# TurboMaster-optimized.net
KiCad netlist of a schematic drawn in EAGLE
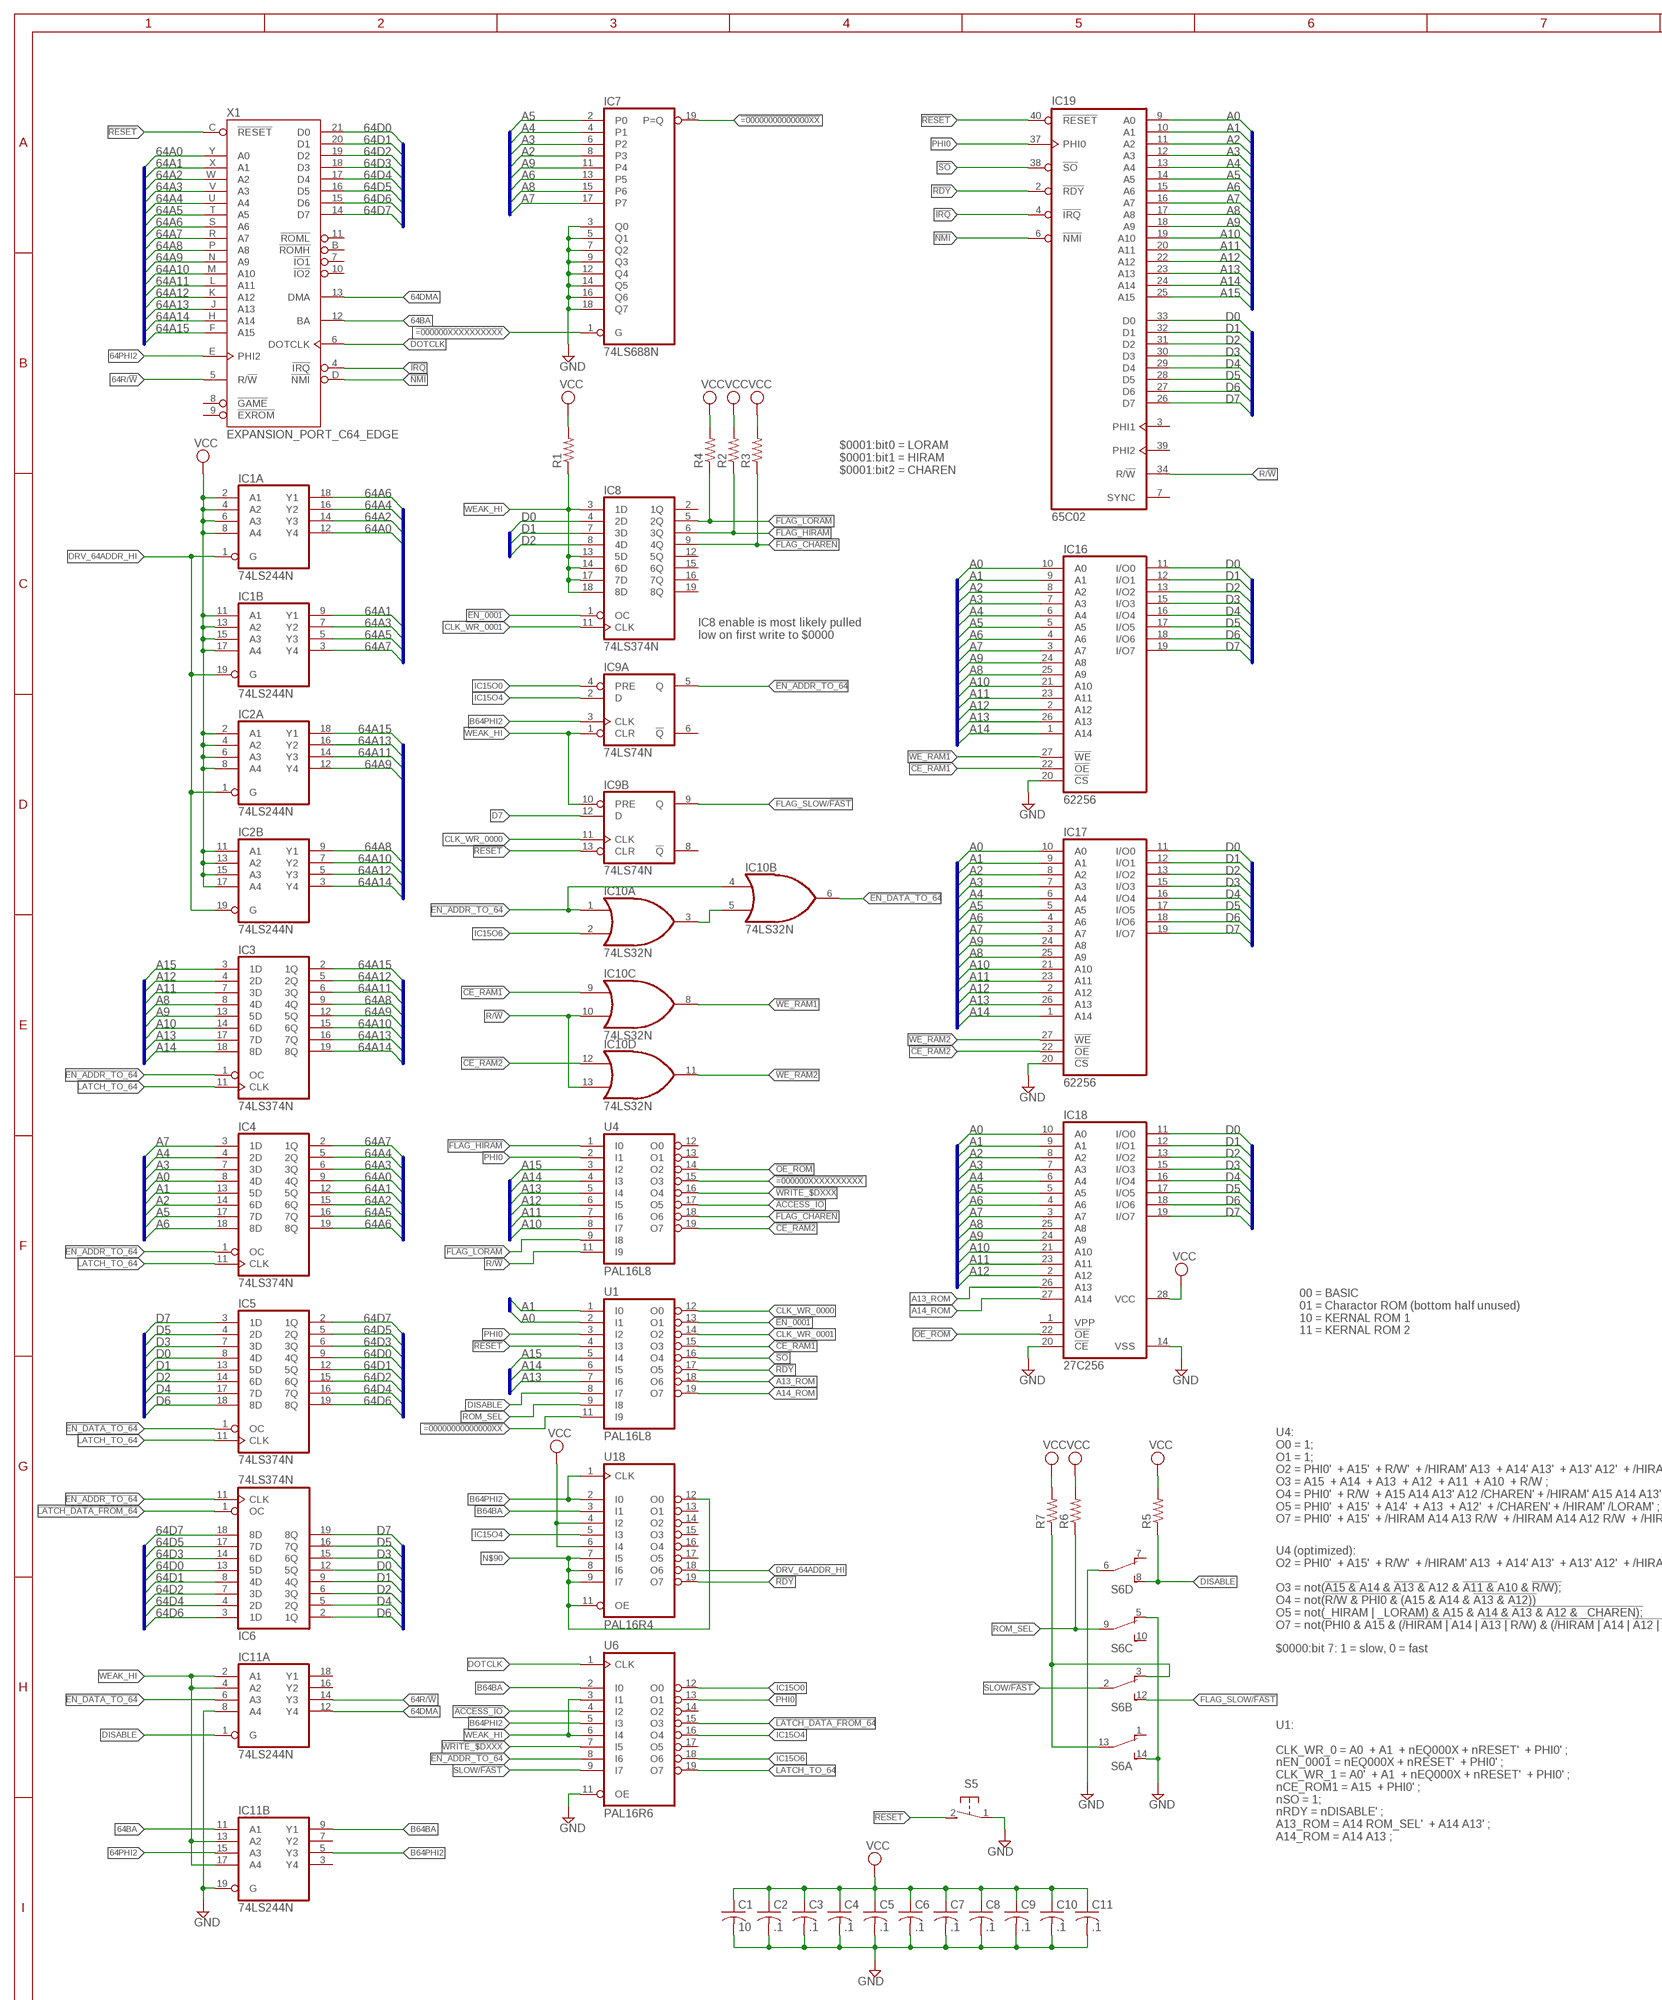
[diagram p0: schematic, sheet 1, part 1 of 2]
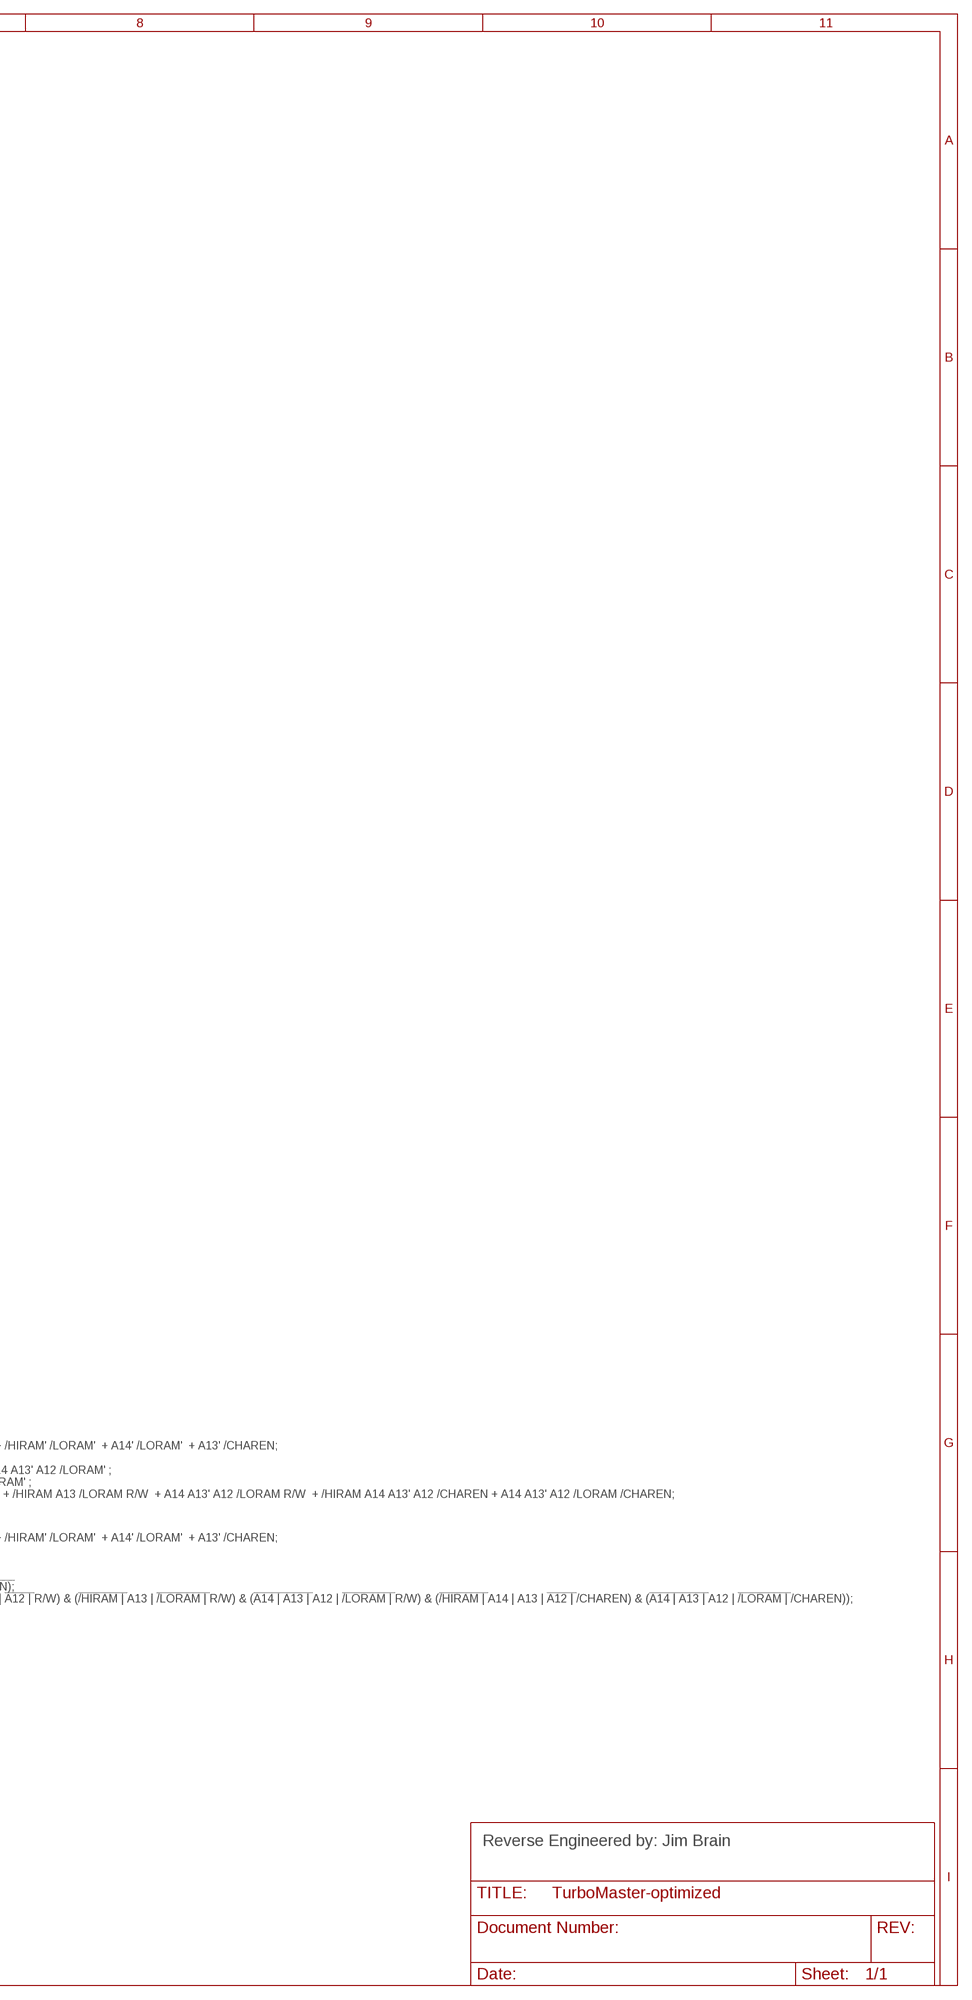
[diagram p1: schematic, sheet 1, part 2 of 2]

(export (version "E")
  (design (tool "Eeschema 10.0.6"))
  (components
    (comp (ref "C1")
      (value "10")
      (footprint "eagle-import:C050-024X044")
      (libsource (lib "eagle-import") (part "C-US050-024X044"))
    )
    (comp (ref "C2")
      (value ".1")
      (footprint "eagle-import:C050-024X044")
      (libsource (lib "eagle-import") (part "C-US050-024X044"))
    )
    (comp (ref "C3")
      (value ".1")
      (footprint "eagle-import:C050-024X044")
      (libsource (lib "eagle-import") (part "C-US050-024X044"))
    )
    (comp (ref "C4")
      (value ".1")
      (footprint "eagle-import:C050-024X044")
      (libsource (lib "eagle-import") (part "C-US050-024X044"))
    )
    (comp (ref "C5")
      (value ".1")
      (footprint "eagle-import:C050-024X044")
      (libsource (lib "eagle-import") (part "C-US050-024X044"))
    )
    (comp (ref "C6")
      (value ".1")
      (footprint "eagle-import:C050-024X044")
      (libsource (lib "eagle-import") (part "C-US050-024X044"))
    )
    (comp (ref "C7")
      (value ".1")
      (footprint "eagle-import:C050-024X044")
      (libsource (lib "eagle-import") (part "C-US050-024X044"))
    )
    (comp (ref "C8")
      (value ".1")
      (footprint "eagle-import:C050-024X044")
      (libsource (lib "eagle-import") (part "C-US050-024X044"))
    )
    (comp (ref "C9")
      (value ".1")
      (footprint "eagle-import:C050-024X044")
      (libsource (lib "eagle-import") (part "C-US050-024X044"))
    )
    (comp (ref "C10")
      (value ".1")
      (footprint "eagle-import:C050-024X044")
      (libsource (lib "eagle-import") (part "C-US050-024X044"))
    )
    (comp (ref "C11")
      (value ".1")
      (footprint "eagle-import:C050-024X044")
      (libsource (lib "eagle-import") (part "C-US050-024X044"))
    )
    (comp (ref "IC1")
      (value "74LS244N")
      (footprint "eagle-import:DIL20")
      (libsource (lib "eagle-import") (part "74244NLS"))
    )
    (comp (ref "IC2")
      (value "74LS244N")
      (footprint "eagle-import:DIL20")
      (libsource (lib "eagle-import") (part "74244NLS"))
    )
    (comp (ref "IC3")
      (value "74LS374N")
      (footprint "eagle-import:DIL20")
      (libsource (lib "eagle-import") (part "74374NLS"))
    )
    (comp (ref "IC4")
      (value "74LS374N")
      (footprint "eagle-import:DIL20")
      (libsource (lib "eagle-import") (part "74374NLS"))
    )
    (comp (ref "IC5")
      (value "74LS374N")
      (footprint "eagle-import:DIL20")
      (libsource (lib "eagle-import") (part "74374NLS"))
    )
    (comp (ref "IC6")
      (value "74LS374N")
      (footprint "eagle-import:DIL20")
      (libsource (lib "eagle-import") (part "74374NLS"))
    )
    (comp (ref "IC7")
      (value "74LS688N")
      (footprint "eagle-import:DIL20")
      (libsource (lib "eagle-import") (part "74688NLS"))
    )
    (comp (ref "IC8")
      (value "74LS374N")
      (footprint "eagle-import:DIL20")
      (libsource (lib "eagle-import") (part "74374NLS"))
    )
    (comp (ref "IC9")
      (value "74LS74N")
      (footprint "eagle-import:DIL14")
      (libsource (lib "eagle-import") (part "7474NLS"))
    )
    (comp (ref "IC10")
      (value "74LS32N")
      (footprint "eagle-import:DIL14")
      (libsource (lib "eagle-import") (part "7432NLS"))
    )
    (comp (ref "IC11")
      (value "74LS244N")
      (footprint "eagle-import:DIL20")
      (libsource (lib "eagle-import") (part "74244NLS"))
    )
    (comp (ref "IC16")
      (value "62256")
      (footprint "eagle-import:DIL28")
      (libsource (lib "eagle-import") (part "62256"))
    )
    (comp (ref "IC17")
      (value "62256")
      (footprint "eagle-import:DIL28")
      (libsource (lib "eagle-import") (part "62256"))
    )
    (comp (ref "IC18")
      (value "27C256")
      (footprint "eagle-import:DIL28-6")
      (libsource (lib "eagle-import") (part "27C256AG"))
    )
    (comp (ref "IC19")
      (value "65C02")
      (footprint "eagle-import:DIL40")
      (libsource (lib "eagle-import") (part "6502C"))
    )
    (comp (ref "R1")
      (value "R-US_0207/10")
      (footprint "eagle-import:0207_10")
      (libsource (lib "eagle-import") (part "R-US_0207/10"))
    )
    (comp (ref "R2")
      (value "R-US_0207/10")
      (footprint "eagle-import:0207_10")
      (libsource (lib "eagle-import") (part "R-US_0207/10"))
    )
    (comp (ref "R3")
      (value "R-US_0207/10")
      (footprint "eagle-import:0207_10")
      (libsource (lib "eagle-import") (part "R-US_0207/10"))
    )
    (comp (ref "R4")
      (value "R-US_0207/10")
      (footprint "eagle-import:0207_10")
      (libsource (lib "eagle-import") (part "R-US_0207/10"))
    )
    (comp (ref "R5")
      (value "R-US_0207/10")
      (footprint "eagle-import:0207_10")
      (libsource (lib "eagle-import") (part "R-US_0207/10"))
    )
    (comp (ref "R6")
      (value "R-US_0207/10")
      (footprint "eagle-import:0207_10")
      (libsource (lib "eagle-import") (part "R-US_0207/10"))
    )
    (comp (ref "R7")
      (value "R-US_0207/10")
      (footprint "eagle-import:0207_10")
      (libsource (lib "eagle-import") (part "R-US_0207/10"))
    )
    (comp (ref "S5")
      (value "31-XX")
      (footprint "eagle-import:B3F-31XX")
      (fields (field (name "MPN") "B3F-3100"))
      (libsource (lib "eagle-import") (part "31-XX"))
    )
    (comp (ref "S6")
      (value "DIP04DPDTS")
      (footprint "eagle-import:DIP04DPDTS")
      (libsource (lib "eagle-import") (part "DIP04DPDTS"))
    )
    (comp (ref "U1")
      (value "PAL16L8")
      (footprint "eagle-import:DIL20")
      (fields (field (name "MF") "TEXAS INSTRUMENTS") (field (name "MPN") "TIBPAL16L8-7CN"))
      (libsource (lib "eagle-import") (part "16L8"))
    )
    (comp (ref "U4")
      (value "PAL16L8")
      (footprint "eagle-import:DIL20")
      (fields (field (name "MF") "TEXAS INSTRUMENTS") (field (name "MPN") "TIBPAL16L8-7CN"))
      (libsource (lib "eagle-import") (part "16L8"))
    )
    (comp (ref "U6")
      (value "PAL16R6")
      (footprint "eagle-import:DIL20")
      (fields (field (name "MPN") "TIBPAL16R6-10CN"))
      (libsource (lib "eagle-import") (part "16R6"))
    )
    (comp (ref "U18")
      (value "PAL16R4")
      (footprint "eagle-import:DIL20")
      (fields (field (name "MF") "TEXAS INSTRUMENTS") (field (name "MPN") "TIBPAL16R4-10CN"))
      (libsource (lib "eagle-import") (part "16R4"))
    )
    (comp (ref "X1")
      (value "EXPANSION_PORT_C64_EDGE")
      (footprint "eagle-import:MA100-22-2")
      (libsource (lib "eagle-import") (part "EXPANSION_PORT_C64_EDGE"))
    )
  )
  (nets
    (net (code "1") (name "/64A0") (class "Default")
      (node (ref "IC1") (pin "12") (pinfunction "Y4_12") (pintype "tri_state"))
      (node (ref "IC4") (pin "9") (pinfunction "4Q_9") (pintype "tri_state"))
      (node (ref "X1") (pin "Y") (pinfunction "A0_Y") (pintype "bidirectional"))
    )
    (net (code "2") (name "/64A1") (class "Default")
      (node (ref "IC1") (pin "9") (pinfunction "Y1_9") (pintype "tri_state"))
      (node (ref "IC4") (pin "12") (pinfunction "5Q_12") (pintype "tri_state"))
      (node (ref "X1") (pin "X") (pinfunction "A1_X") (pintype "bidirectional"))
    )
    (net (code "3") (name "/64A2") (class "Default")
      (node (ref "IC1") (pin "14") (pinfunction "Y3_14") (pintype "tri_state"))
      (node (ref "IC4") (pin "15") (pinfunction "6Q_15") (pintype "tri_state"))
      (node (ref "X1") (pin "W") (pinfunction "A2_W") (pintype "bidirectional"))
    )
    (net (code "4") (name "/64A3") (class "Default")
      (node (ref "IC1") (pin "7") (pinfunction "Y2_7") (pintype "tri_state"))
      (node (ref "IC4") (pin "6") (pinfunction "3Q_6") (pintype "tri_state"))
      (node (ref "X1") (pin "V") (pinfunction "A3_V") (pintype "bidirectional"))
    )
    (net (code "5") (name "/64A4") (class "Default")
      (node (ref "IC1") (pin "16") (pinfunction "Y2_16") (pintype "tri_state"))
      (node (ref "IC4") (pin "5") (pinfunction "2Q_5") (pintype "tri_state"))
      (node (ref "X1") (pin "U") (pinfunction "A4_U") (pintype "bidirectional"))
    )
    (net (code "6") (name "/64A5") (class "Default")
      (node (ref "IC1") (pin "5") (pinfunction "Y3_5") (pintype "tri_state"))
      (node (ref "IC4") (pin "16") (pinfunction "7Q_16") (pintype "tri_state"))
      (node (ref "X1") (pin "T") (pinfunction "A5_T") (pintype "bidirectional"))
    )
    (net (code "7") (name "/64A6") (class "Default")
      (node (ref "IC1") (pin "18") (pinfunction "Y1_18") (pintype "tri_state"))
      (node (ref "IC4") (pin "19") (pinfunction "8Q_19") (pintype "tri_state"))
      (node (ref "X1") (pin "S") (pinfunction "A6_S") (pintype "bidirectional"))
    )
    (net (code "8") (name "/64A7") (class "Default")
      (node (ref "IC1") (pin "3") (pinfunction "Y4_3") (pintype "tri_state"))
      (node (ref "IC4") (pin "2") (pinfunction "1Q_2") (pintype "tri_state"))
      (node (ref "X1") (pin "R") (pinfunction "A7_R") (pintype "bidirectional"))
    )
    (net (code "9") (name "/64A8") (class "Default")
      (node (ref "IC2") (pin "9") (pinfunction "Y1_9") (pintype "tri_state"))
      (node (ref "IC3") (pin "9") (pinfunction "4Q_9") (pintype "tri_state"))
      (node (ref "X1") (pin "P") (pinfunction "A8_P") (pintype "bidirectional"))
    )
    (net (code "10") (name "/64A9") (class "Default")
      (node (ref "IC2") (pin "12") (pinfunction "Y4_12") (pintype "tri_state"))
      (node (ref "IC3") (pin "12") (pinfunction "5Q_12") (pintype "tri_state"))
      (node (ref "X1") (pin "N") (pinfunction "A9_N") (pintype "bidirectional"))
    )
    (net (code "11") (name "/64A10") (class "Default")
      (node (ref "IC2") (pin "7") (pinfunction "Y2_7") (pintype "tri_state"))
      (node (ref "IC3") (pin "15") (pinfunction "6Q_15") (pintype "tri_state"))
      (node (ref "X1") (pin "M") (pinfunction "A10_M") (pintype "bidirectional"))
    )
    (net (code "12") (name "/64A11") (class "Default")
      (node (ref "IC2") (pin "14") (pinfunction "Y3_14") (pintype "tri_state"))
      (node (ref "IC3") (pin "6") (pinfunction "3Q_6") (pintype "tri_state"))
      (node (ref "X1") (pin "L") (pinfunction "A11_L") (pintype "bidirectional"))
    )
    (net (code "13") (name "/64A12") (class "Default")
      (node (ref "IC2") (pin "5") (pinfunction "Y3_5") (pintype "tri_state"))
      (node (ref "IC3") (pin "5") (pinfunction "2Q_5") (pintype "tri_state"))
      (node (ref "X1") (pin "K") (pinfunction "A12_K") (pintype "bidirectional"))
    )
    (net (code "14") (name "/64A13") (class "Default")
      (node (ref "IC2") (pin "16") (pinfunction "Y2_16") (pintype "tri_state"))
      (node (ref "IC3") (pin "16") (pinfunction "7Q_16") (pintype "tri_state"))
      (node (ref "X1") (pin "J") (pinfunction "A13_J") (pintype "bidirectional"))
    )
    (net (code "15") (name "/64A14") (class "Default")
      (node (ref "IC2") (pin "3") (pinfunction "Y4_3") (pintype "tri_state"))
      (node (ref "IC3") (pin "19") (pinfunction "8Q_19") (pintype "tri_state"))
      (node (ref "X1") (pin "H") (pinfunction "A14_H") (pintype "bidirectional"))
    )
    (net (code "16") (name "/64A15") (class "Default")
      (node (ref "IC2") (pin "18") (pinfunction "Y1_18") (pintype "tri_state"))
      (node (ref "IC3") (pin "2") (pinfunction "1Q_2") (pintype "tri_state"))
      (node (ref "X1") (pin "F") (pinfunction "A15_F") (pintype "bidirectional"))
    )
    (net (code "17") (name "/64D0") (class "Default")
      (node (ref "IC5") (pin "9") (pinfunction "4Q_9") (pintype "tri_state"))
      (node (ref "IC6") (pin "13") (pinfunction "5D_13") (pintype "input"))
      (node (ref "X1") (pin "21") (pinfunction "D0_21") (pintype "bidirectional"))
    )
    (net (code "18") (name "/64D1") (class "Default")
      (node (ref "IC5") (pin "12") (pinfunction "5Q_12") (pintype "tri_state"))
      (node (ref "IC6") (pin "8") (pinfunction "4D_8") (pintype "input"))
      (node (ref "X1") (pin "20") (pinfunction "D1_20") (pintype "bidirectional"))
    )
    (net (code "19") (name "/64D2") (class "Default")
      (node (ref "IC5") (pin "15") (pinfunction "6Q_15") (pintype "tri_state"))
      (node (ref "IC6") (pin "7") (pinfunction "3D_7") (pintype "input"))
      (node (ref "X1") (pin "19") (pinfunction "D2_19") (pintype "bidirectional"))
    )
    (net (code "20") (name "/64D3") (class "Default")
      (node (ref "IC5") (pin "6") (pinfunction "3Q_6") (pintype "tri_state"))
      (node (ref "IC6") (pin "14") (pinfunction "6D_14") (pintype "input"))
      (node (ref "X1") (pin "18") (pinfunction "D3_18") (pintype "bidirectional"))
    )
    (net (code "21") (name "/64D4") (class "Default")
      (node (ref "IC5") (pin "16") (pinfunction "7Q_16") (pintype "tri_state"))
      (node (ref "IC6") (pin "4") (pinfunction "2D_4") (pintype "input"))
      (node (ref "X1") (pin "17") (pinfunction "D4_17") (pintype "bidirectional"))
    )
    (net (code "22") (name "/64D5") (class "Default")
      (node (ref "IC5") (pin "5") (pinfunction "2Q_5") (pintype "tri_state"))
      (node (ref "IC6") (pin "17") (pinfunction "7D_17") (pintype "input"))
      (node (ref "X1") (pin "16") (pinfunction "D5_16") (pintype "bidirectional"))
    )
    (net (code "23") (name "/64D6") (class "Default")
      (node (ref "IC5") (pin "19") (pinfunction "8Q_19") (pintype "tri_state"))
      (node (ref "IC6") (pin "3") (pinfunction "1D_3") (pintype "input"))
      (node (ref "X1") (pin "15") (pinfunction "D6_15") (pintype "bidirectional"))
    )
    (net (code "24") (name "/64D7") (class "Default")
      (node (ref "IC5") (pin "2") (pinfunction "1Q_2") (pintype "tri_state"))
      (node (ref "IC6") (pin "18") (pinfunction "8D_18") (pintype "input"))
      (node (ref "X1") (pin "14") (pinfunction "D7_14") (pintype "bidirectional"))
    )
    (net (code "25") (name "/64R{slash}~{W}") (class "Default")
      (node (ref "IC11") (pin "14") (pinfunction "Y3_14") (pintype "tri_state"))
      (node (ref "X1") (pin "5") (pinfunction "R/~{W}_5") (pintype "bidirectional"))
    )
    (net (code "26") (name "/A0") (class "Default")
      (node (ref "IC16") (pin "10") (pinfunction "A0_10") (pintype "input"))
      (node (ref "IC17") (pin "10") (pinfunction "A0_10") (pintype "input"))
      (node (ref "IC18") (pin "10") (pinfunction "A0_10") (pintype "input"))
      (node (ref "IC19") (pin "9") (pinfunction "A0_9") (pintype "output"))
      (node (ref "IC4") (pin "8") (pinfunction "4D_8") (pintype "input"))
      (node (ref "U1") (pin "2") (pinfunction "I1_2") (pintype "input"))
    )
    (net (code "27") (name "/A1") (class "Default")
      (node (ref "IC16") (pin "9") (pinfunction "A1_9") (pintype "input"))
      (node (ref "IC17") (pin "9") (pinfunction "A1_9") (pintype "input"))
      (node (ref "IC18") (pin "9") (pinfunction "A1_9") (pintype "input"))
      (node (ref "IC19") (pin "10") (pinfunction "A1_10") (pintype "output"))
      (node (ref "IC4") (pin "13") (pinfunction "5D_13") (pintype "input"))
      (node (ref "U1") (pin "1") (pinfunction "I0_1") (pintype "input"))
    )
    (net (code "28") (name "/A2") (class "Default")
      (node (ref "IC16") (pin "8") (pinfunction "A2_8") (pintype "input"))
      (node (ref "IC17") (pin "8") (pinfunction "A2_8") (pintype "input"))
      (node (ref "IC18") (pin "8") (pinfunction "A2_8") (pintype "input"))
      (node (ref "IC19") (pin "11") (pinfunction "A2_11") (pintype "output"))
      (node (ref "IC4") (pin "14") (pinfunction "6D_14") (pintype "input"))
      (node (ref "IC7") (pin "8") (pinfunction "P3_8") (pintype "input"))
    )
    (net (code "29") (name "/A3") (class "Default")
      (node (ref "IC16") (pin "7") (pinfunction "A3_7") (pintype "input"))
      (node (ref "IC17") (pin "7") (pinfunction "A3_7") (pintype "input"))
      (node (ref "IC18") (pin "7") (pinfunction "A3_7") (pintype "input"))
      (node (ref "IC19") (pin "12") (pinfunction "A3_12") (pintype "output"))
      (node (ref "IC4") (pin "7") (pinfunction "3D_7") (pintype "input"))
      (node (ref "IC7") (pin "6") (pinfunction "P2_6") (pintype "input"))
    )
    (net (code "30") (name "/A4") (class "Default")
      (node (ref "IC16") (pin "6") (pinfunction "A4_6") (pintype "input"))
      (node (ref "IC17") (pin "6") (pinfunction "A4_6") (pintype "input"))
      (node (ref "IC18") (pin "6") (pinfunction "A4_6") (pintype "input"))
      (node (ref "IC19") (pin "13") (pinfunction "A4_13") (pintype "output"))
      (node (ref "IC4") (pin "4") (pinfunction "2D_4") (pintype "input"))
      (node (ref "IC7") (pin "4") (pinfunction "P1_4") (pintype "input"))
    )
    (net (code "31") (name "/A5") (class "Default")
      (node (ref "IC16") (pin "5") (pinfunction "A5_5") (pintype "input"))
      (node (ref "IC17") (pin "5") (pinfunction "A5_5") (pintype "input"))
      (node (ref "IC18") (pin "5") (pinfunction "A5_5") (pintype "input"))
      (node (ref "IC19") (pin "14") (pinfunction "A5_14") (pintype "output"))
      (node (ref "IC4") (pin "17") (pinfunction "7D_17") (pintype "input"))
      (node (ref "IC7") (pin "2") (pinfunction "P0_2") (pintype "input"))
    )
    (net (code "32") (name "/A6") (class "Default")
      (node (ref "IC16") (pin "4") (pinfunction "A6_4") (pintype "input"))
      (node (ref "IC17") (pin "4") (pinfunction "A6_4") (pintype "input"))
      (node (ref "IC18") (pin "4") (pinfunction "A6_4") (pintype "input"))
      (node (ref "IC19") (pin "15") (pinfunction "A6_15") (pintype "output"))
      (node (ref "IC4") (pin "18") (pinfunction "8D_18") (pintype "input"))
      (node (ref "IC7") (pin "13") (pinfunction "P5_13") (pintype "input"))
    )
    (net (code "33") (name "/A7") (class "Default")
      (node (ref "IC16") (pin "3") (pinfunction "A7_3") (pintype "input"))
      (node (ref "IC17") (pin "3") (pinfunction "A7_3") (pintype "input"))
      (node (ref "IC18") (pin "3") (pinfunction "A7_3") (pintype "input"))
      (node (ref "IC19") (pin "16") (pinfunction "A7_16") (pintype "output"))
      (node (ref "IC4") (pin "3") (pinfunction "1D_3") (pintype "input"))
      (node (ref "IC7") (pin "17") (pinfunction "P7_17") (pintype "input"))
    )
    (net (code "34") (name "/A8") (class "Default")
      (node (ref "IC16") (pin "25") (pinfunction "A9_25") (pintype "input"))
      (node (ref "IC17") (pin "25") (pinfunction "A9_25") (pintype "input"))
      (node (ref "IC18") (pin "25") (pinfunction "A8_25") (pintype "input"))
      (node (ref "IC19") (pin "17") (pinfunction "A8_17") (pintype "output"))
      (node (ref "IC3") (pin "8") (pinfunction "4D_8") (pintype "input"))
      (node (ref "IC7") (pin "15") (pinfunction "P6_15") (pintype "input"))
    )
    (net (code "35") (name "/A9") (class "Default")
      (node (ref "IC16") (pin "24") (pinfunction "A8_24") (pintype "input"))
      (node (ref "IC17") (pin "24") (pinfunction "A8_24") (pintype "input"))
      (node (ref "IC18") (pin "24") (pinfunction "A9_24") (pintype "input"))
      (node (ref "IC19") (pin "18") (pinfunction "A9_18") (pintype "output"))
      (node (ref "IC3") (pin "13") (pinfunction "5D_13") (pintype "input"))
      (node (ref "IC7") (pin "11") (pinfunction "P4_11") (pintype "input"))
    )
    (net (code "36") (name "/A10") (class "Default")
      (node (ref "IC16") (pin "21") (pinfunction "A10_21") (pintype "input"))
      (node (ref "IC17") (pin "21") (pinfunction "A10_21") (pintype "input"))
      (node (ref "IC18") (pin "21") (pinfunction "A10_21") (pintype "input"))
      (node (ref "IC19") (pin "19") (pinfunction "A10_19") (pintype "output"))
      (node (ref "IC3") (pin "14") (pinfunction "6D_14") (pintype "input"))
      (node (ref "U4") (pin "8") (pinfunction "I7_8") (pintype "input"))
    )
    (net (code "37") (name "/A11") (class "Default")
      (node (ref "IC16") (pin "23") (pinfunction "A11_23") (pintype "input"))
      (node (ref "IC17") (pin "23") (pinfunction "A11_23") (pintype "input"))
      (node (ref "IC18") (pin "23") (pinfunction "A11_23") (pintype "input"))
      (node (ref "IC19") (pin "20") (pinfunction "A11_20") (pintype "output"))
      (node (ref "IC3") (pin "7") (pinfunction "3D_7") (pintype "input"))
      (node (ref "U4") (pin "7") (pinfunction "I6_7") (pintype "input"))
    )
    (net (code "38") (name "/A12") (class "Default")
      (node (ref "IC16") (pin "2") (pinfunction "A12_2") (pintype "input"))
      (node (ref "IC17") (pin "2") (pinfunction "A12_2") (pintype "input"))
      (node (ref "IC18") (pin "2") (pinfunction "A12_2") (pintype "input"))
      (node (ref "IC19") (pin "22") (pinfunction "A12_22") (pintype "output"))
      (node (ref "IC3") (pin "4") (pinfunction "2D_4") (pintype "input"))
      (node (ref "U4") (pin "6") (pinfunction "I5_6") (pintype "input"))
    )
    (net (code "39") (name "/A13") (class "Default")
      (node (ref "IC16") (pin "26") (pinfunction "A13_26") (pintype "input"))
      (node (ref "IC17") (pin "26") (pinfunction "A13_26") (pintype "input"))
      (node (ref "IC19") (pin "23") (pinfunction "A13_23") (pintype "output"))
      (node (ref "IC3") (pin "17") (pinfunction "7D_17") (pintype "input"))
      (node (ref "U1") (pin "7") (pinfunction "I6_7") (pintype "input"))
      (node (ref "U4") (pin "5") (pinfunction "I4_5") (pintype "input"))
    )
    (net (code "40") (name "/A14") (class "Default")
      (node (ref "IC16") (pin "1") (pinfunction "A14_1") (pintype "input"))
      (node (ref "IC17") (pin "1") (pinfunction "A14_1") (pintype "input"))
      (node (ref "IC19") (pin "24") (pinfunction "A14_24") (pintype "output"))
      (node (ref "IC3") (pin "18") (pinfunction "8D_18") (pintype "input"))
      (node (ref "U1") (pin "6") (pinfunction "I5_6") (pintype "input"))
      (node (ref "U4") (pin "4") (pinfunction "I3_4") (pintype "input"))
    )
    (net (code "41") (name "/A15") (class "Default")
      (node (ref "IC19") (pin "25") (pinfunction "A15_25") (pintype "output"))
      (node (ref "IC3") (pin "3") (pinfunction "1D_3") (pintype "input"))
      (node (ref "U1") (pin "5") (pinfunction "I4_5") (pintype "input"))
      (node (ref "U4") (pin "3") (pinfunction "I2_3") (pintype "input"))
    )
    (net (code "42") (name "/D0") (class "Default")
      (node (ref "IC16") (pin "11") (pinfunction "I/O0_11") (pintype "bidirectional"))
      (node (ref "IC17") (pin "11") (pinfunction "I/O0_11") (pintype "bidirectional"))
      (node (ref "IC18") (pin "11") (pinfunction "I/O0_11") (pintype "tri_state"))
      (node (ref "IC19") (pin "33") (pinfunction "D0_33") (pintype "bidirectional"))
      (node (ref "IC5") (pin "8") (pinfunction "4D_8") (pintype "input"))
      (node (ref "IC6") (pin "12") (pinfunction "5Q_12") (pintype "tri_state"))
      (node (ref "IC8") (pin "4") (pinfunction "2D_4") (pintype "input"))
    )
    (net (code "43") (name "/D1") (class "Default")
      (node (ref "IC16") (pin "12") (pinfunction "I/O1_12") (pintype "bidirectional"))
      (node (ref "IC17") (pin "12") (pinfunction "I/O1_12") (pintype "bidirectional"))
      (node (ref "IC18") (pin "12") (pinfunction "I/O1_12") (pintype "tri_state"))
      (node (ref "IC19") (pin "32") (pinfunction "D1_32") (pintype "bidirectional"))
      (node (ref "IC5") (pin "13") (pinfunction "5D_13") (pintype "input"))
      (node (ref "IC6") (pin "9") (pinfunction "4Q_9") (pintype "tri_state"))
      (node (ref "IC8") (pin "7") (pinfunction "3D_7") (pintype "input"))
    )
    (net (code "44") (name "/D2") (class "Default")
      (node (ref "IC16") (pin "13") (pinfunction "I/O2_13") (pintype "bidirectional"))
      (node (ref "IC17") (pin "13") (pinfunction "I/O2_13") (pintype "bidirectional"))
      (node (ref "IC18") (pin "13") (pinfunction "I/O2_13") (pintype "tri_state"))
      (node (ref "IC19") (pin "31") (pinfunction "D2_31") (pintype "bidirectional"))
      (node (ref "IC5") (pin "14") (pinfunction "6D_14") (pintype "input"))
      (node (ref "IC6") (pin "6") (pinfunction "3Q_6") (pintype "tri_state"))
      (node (ref "IC8") (pin "8") (pinfunction "4D_8") (pintype "input"))
    )
    (net (code "45") (name "/D3") (class "Default")
      (node (ref "IC16") (pin "15") (pinfunction "I/O3_15") (pintype "bidirectional"))
      (node (ref "IC17") (pin "15") (pinfunction "I/O3_15") (pintype "bidirectional"))
      (node (ref "IC18") (pin "15") (pinfunction "I/O3_15") (pintype "tri_state"))
      (node (ref "IC19") (pin "30") (pinfunction "D3_30") (pintype "bidirectional"))
      (node (ref "IC5") (pin "7") (pinfunction "3D_7") (pintype "input"))
      (node (ref "IC6") (pin "15") (pinfunction "6Q_15") (pintype "tri_state"))
    )
    (net (code "46") (name "/D4") (class "Default")
      (node (ref "IC16") (pin "16") (pinfunction "I/O4_16") (pintype "bidirectional"))
      (node (ref "IC17") (pin "16") (pinfunction "I/O4_16") (pintype "bidirectional"))
      (node (ref "IC18") (pin "16") (pinfunction "I/O4_16") (pintype "tri_state"))
      (node (ref "IC19") (pin "29") (pinfunction "D4_29") (pintype "bidirectional"))
      (node (ref "IC5") (pin "17") (pinfunction "7D_17") (pintype "input"))
      (node (ref "IC6") (pin "5") (pinfunction "2Q_5") (pintype "tri_state"))
    )
    (net (code "47") (name "/D5") (class "Default")
      (node (ref "IC16") (pin "17") (pinfunction "I/O5_17") (pintype "bidirectional"))
      (node (ref "IC17") (pin "17") (pinfunction "I/O5_17") (pintype "bidirectional"))
      (node (ref "IC18") (pin "17") (pinfunction "I/O5_17") (pintype "tri_state"))
      (node (ref "IC19") (pin "28") (pinfunction "D5_28") (pintype "bidirectional"))
      (node (ref "IC5") (pin "4") (pinfunction "2D_4") (pintype "input"))
      (node (ref "IC6") (pin "16") (pinfunction "7Q_16") (pintype "tri_state"))
    )
    (net (code "48") (name "/D6") (class "Default")
      (node (ref "IC16") (pin "18") (pinfunction "I/O6_18") (pintype "bidirectional"))
      (node (ref "IC17") (pin "18") (pinfunction "I/O6_18") (pintype "bidirectional"))
      (node (ref "IC18") (pin "18") (pinfunction "I/O6_18") (pintype "tri_state"))
      (node (ref "IC19") (pin "27") (pinfunction "D6_27") (pintype "bidirectional"))
      (node (ref "IC5") (pin "18") (pinfunction "8D_18") (pintype "input"))
      (node (ref "IC6") (pin "2") (pinfunction "1Q_2") (pintype "tri_state"))
    )
    (net (code "49") (name "/FLAG_SLOW{slash}~{FAST}") (class "Default")
      (node (ref "IC9") (pin "9") (pinfunction "Q_9") (pintype "output"))
      (node (ref "S6") (pin "12") (pinfunction "S_12") (pintype "passive"))
    )
    (net (code "50") (name "/R{slash}~{W}") (class "Default")
      (node (ref "IC10") (pin "10") (pinfunction "I1_10") (pintype "input"))
      (node (ref "IC10") (pin "13") (pinfunction "I1_13") (pintype "input"))
      (node (ref "IC19") (pin "34") (pinfunction "R/~{W}_34") (pintype "output"))
      (node (ref "U4") (pin "11") (pinfunction "I9_11") (pintype "input"))
    )
    (net (code "51") (name "/SLOW{slash}~{FAST}") (class "Default")
      (node (ref "S6") (pin "2") (pinfunction "P_2") (pintype "passive"))
      (node (ref "U6") (pin "9") (pinfunction "I7_9") (pintype "input"))
    )
    (net (code "52") (name "/~{=000000XXXXXXXXXX}") (class "Default")
      (node (ref "IC7") (pin "1") (pinfunction "G_1") (pintype "input"))
      (node (ref "U4") (pin "15") (pinfunction "O3_15") (pintype "bidirectional"))
    )
    (net (code "53") (name "/~{=00000000000000XX}") (class "Default")
      (node (ref "IC7") (pin "19") (pinfunction "P=Q_19") (pintype "output"))
      (node (ref "U1") (pin "11") (pinfunction "I9_11") (pintype "input"))
    )
    (net (code "54") (name "/~{ACCESS_IO}") (class "Default")
      (node (ref "U4") (pin "17") (pinfunction "O5_17") (pintype "bidirectional"))
      (node (ref "U6") (pin "4") (pinfunction "I2_4") (pintype "input"))
    )
    (net (code "55") (name "/~{CE_RAM1}") (class "Default")
      (node (ref "IC10") (pin "9") (pinfunction "I0_9") (pintype "input"))
      (node (ref "IC16") (pin "22") (pinfunction "~{OE}_22") (pintype "input"))
      (node (ref "U1") (pin "15") (pinfunction "O3_15") (pintype "bidirectional"))
    )
    (net (code "56") (name "/~{CE_RAM2}") (class "Default")
      (node (ref "IC10") (pin "12") (pinfunction "I0_12") (pintype "input"))
      (node (ref "IC17") (pin "22") (pinfunction "~{OE}_22") (pintype "input"))
      (node (ref "U4") (pin "19") (pinfunction "O7_19") (pintype "output"))
    )
    (net (code "57") (name "/~{EN_0001}") (class "Default")
      (node (ref "IC8") (pin "1") (pinfunction "OC_1") (pintype "input"))
      (node (ref "U1") (pin "13") (pinfunction "O1_13") (pintype "bidirectional"))
    )
    (net (code "58") (name "/~{EN_ADDR_TO_64}") (class "Default")
      (node (ref "IC10") (pin "1") (pinfunction "I0_1") (pintype "input"))
      (node (ref "IC10") (pin "4") (pinfunction "I0_4") (pintype "input"))
      (node (ref "IC3") (pin "1") (pinfunction "OC_1") (pintype "input"))
      (node (ref "IC4") (pin "1") (pinfunction "OC_1") (pintype "input"))
      (node (ref "IC6") (pin "11") (pinfunction "CLK_11") (pintype "input"))
      (node (ref "IC9") (pin "5") (pinfunction "Q_5") (pintype "output"))
      (node (ref "U6") (pin "8") (pinfunction "I6_8") (pintype "input"))
    )
    (net (code "59") (name "/~{EN_DATA_TO_64}") (class "Default")
      (node (ref "IC10") (pin "6") (pinfunction "O_6") (pintype "output"))
      (node (ref "IC11") (pin "6") (pinfunction "A3_6") (pintype "input"))
      (node (ref "IC5") (pin "1") (pinfunction "OC_1") (pintype "input"))
    )
    (net (code "60") (name "/~{FLAG_CHAREN}") (class "Default")
      (node (ref "IC8") (pin "9") (pinfunction "4Q_9") (pintype "tri_state"))
      (node (ref "R3") (pin "1") (pinfunction "1_1") (pintype "passive"))
      (node (ref "U4") (pin "18") (pinfunction "O6_18") (pintype "bidirectional"))
    )
    (net (code "61") (name "/~{FLAG_HIRAM}") (class "Default")
      (node (ref "IC8") (pin "6") (pinfunction "3Q_6") (pintype "tri_state"))
      (node (ref "R2") (pin "1") (pinfunction "1_1") (pintype "passive"))
      (node (ref "U4") (pin "1") (pinfunction "I0_1") (pintype "input"))
    )
    (net (code "62") (name "/~{FLAG_LORAM}") (class "Default")
      (node (ref "IC8") (pin "5") (pinfunction "2Q_5") (pintype "tri_state"))
      (node (ref "R4") (pin "1") (pinfunction "1_1") (pintype "passive"))
      (node (ref "U4") (pin "9") (pinfunction "I8_9") (pintype "input"))
    )
    (net (code "63") (name "/~{IRQ}") (class "Default")
      (node (ref "IC19") (pin "4") (pinfunction "~{IRQ}_4") (pintype "input"))
      (node (ref "X1") (pin "4") (pinfunction "~{IRQ}_4") (pintype "bidirectional"))
    )
    (net (code "64") (name "/~{LATCH_DATA_FROM_64}") (class "Default")
      (node (ref "IC6") (pin "1") (pinfunction "OC_1") (pintype "input"))
      (node (ref "U6") (pin "15") (pinfunction "O3_15") (pintype "output"))
    )
    (net (code "65") (name "/~{NMI}") (class "Default")
      (node (ref "IC19") (pin "6") (pinfunction "~{NMI}_6") (pintype "input"))
      (node (ref "X1") (pin "D") (pinfunction "~{NMI}_D") (pintype "bidirectional"))
    )
    (net (code "66") (name "/~{OE_ROM}") (class "Default")
      (node (ref "IC18") (pin "22") (pinfunction "~{OE}_22") (pintype "input"))
      (node (ref "U4") (pin "14") (pinfunction "O2_14") (pintype "bidirectional"))
    )
    (net (code "67") (name "/~{RDY}") (class "Default")
      (node (ref "IC19") (pin "2") (pinfunction "~{RDY}_2") (pintype "input"))
      (node (ref "U1") (pin "17") (pinfunction "O5_17") (pintype "bidirectional"))
      (node (ref "U18") (pin "19") (pinfunction "O7_19") (pintype "bidirectional"))
    )
    (net (code "68") (name "/~{RESET}") (class "Default")
      (node (ref "IC19") (pin "40") (pinfunction "~{RESET}_40") (pintype "input"))
      (node (ref "IC9") (pin "13") (pinfunction "CLR_13") (pintype "input"))
      (node (ref "S5") (pin "2") (pinfunction "S_2") (pintype "passive"))
      (node (ref "U1") (pin "4") (pinfunction "I3_4") (pintype "input"))
      (node (ref "X1") (pin "C") (pinfunction "~{RESET}_C") (pintype "bidirectional"))
    )
    (net (code "69") (name "/~{SO}") (class "Default")
      (node (ref "IC19") (pin "38") (pinfunction "~{SO}_38") (pintype "input"))
      (node (ref "U1") (pin "16") (pinfunction "O4_16") (pintype "bidirectional"))
    )
    (net (code "70") (name "/~{WE_RAM1}") (class "Default")
      (node (ref "IC10") (pin "8") (pinfunction "O_8") (pintype "output"))
      (node (ref "IC16") (pin "27") (pinfunction "~{WE}_27") (pintype "input"))
    )
    (net (code "71") (name "/~{WE_RAM2}") (class "Default")
      (node (ref "IC10") (pin "11") (pinfunction "O_11") (pintype "output"))
      (node (ref "IC17") (pin "27") (pinfunction "~{WE}_27") (pintype "input"))
    )
    (net (code "72") (name "/~{WRITE_$DXXX}") (class "Default")
      (node (ref "U4") (pin "16") (pinfunction "O4_16") (pintype "bidirectional"))
      (node (ref "U6") (pin "7") (pinfunction "I5_7") (pintype "input"))
    )
    (net (code "73") (name "64BA") (class "Default")
      (node (ref "IC11") (pin "11") (pinfunction "A1_11") (pintype "input"))
      (node (ref "X1") (pin "12") (pinfunction "BA_12") (pintype "bidirectional"))
    )
    (net (code "74") (name "64DMA") (class "Default")
      (node (ref "IC11") (pin "12") (pinfunction "Y4_12") (pintype "tri_state"))
      (node (ref "X1") (pin "13") (pinfunction "DMA_13") (pintype "bidirectional"))
    )
    (net (code "75") (name "64PHI2") (class "Default")
      (node (ref "IC11") (pin "15") (pinfunction "A3_15") (pintype "input"))
      (node (ref "X1") (pin "E") (pinfunction "PHI2_E") (pintype "bidirectional"))
    )
    (net (code "76") (name "A13_ROM") (class "Default")
      (node (ref "IC18") (pin "26") (pinfunction "A13_26") (pintype "input"))
      (node (ref "U1") (pin "18") (pinfunction "O6_18") (pintype "bidirectional"))
    )
    (net (code "77") (name "A14_ROM") (class "Default")
      (node (ref "IC18") (pin "27") (pinfunction "A14_27") (pintype "input"))
      (node (ref "U1") (pin "19") (pinfunction "O7_19") (pintype "output"))
    )
    (net (code "78") (name "B64BA") (class "Default")
      (node (ref "IC11") (pin "9") (pinfunction "Y1_9") (pintype "tri_state"))
      (node (ref "U18") (pin "3") (pinfunction "I1_3") (pintype "input"))
      (node (ref "U6") (pin "2") (pinfunction "I0_2") (pintype "input"))
    )
    (net (code "79") (name "B64PHI2") (class "Default")
      (node (ref "IC11") (pin "5") (pinfunction "Y3_5") (pintype "tri_state"))
      (node (ref "IC9") (pin "3") (pinfunction "CLK_3") (pintype "input"))
      (node (ref "U18") (pin "1") (pinfunction "CLK_1") (pintype "input"))
      (node (ref "U18") (pin "2") (pinfunction "I0_2") (pintype "input"))
      (node (ref "U6") (pin "5") (pinfunction "I3_5") (pintype "input"))
    )
    (net (code "80") (name "CLK_WR_0000") (class "Default")
      (node (ref "IC9") (pin "11") (pinfunction "CLK_11") (pintype "input"))
      (node (ref "U1") (pin "12") (pinfunction "O0_12") (pintype "output"))
    )
    (net (code "81") (name "CLK_WR_0001") (class "Default")
      (node (ref "IC8") (pin "11") (pinfunction "CLK_11") (pintype "input"))
      (node (ref "U1") (pin "14") (pinfunction "O2_14") (pintype "bidirectional"))
    )
    (net (code "82") (name "D7") (class "Default")
      (node (ref "IC16") (pin "19") (pinfunction "I/O7_19") (pintype "bidirectional"))
      (node (ref "IC17") (pin "19") (pinfunction "I/O7_19") (pintype "bidirectional"))
      (node (ref "IC18") (pin "19") (pinfunction "I/O7_19") (pintype "tri_state"))
      (node (ref "IC19") (pin "26") (pinfunction "D7_26") (pintype "bidirectional"))
      (node (ref "IC5") (pin "3") (pinfunction "1D_3") (pintype "input"))
      (node (ref "IC6") (pin "19") (pinfunction "8Q_19") (pintype "tri_state"))
      (node (ref "IC9") (pin "12") (pinfunction "D_12") (pintype "input"))
    )
    (net (code "83") (name "DISABLE") (class "Default")
      (node (ref "IC11") (pin "1") (pinfunction "G_1") (pintype "input"))
      (node (ref "R5") (pin "1") (pinfunction "1_1") (pintype "passive"))
      (node (ref "S6") (pin "8") (pinfunction "S_8") (pintype "passive"))
      (node (ref "U1") (pin "8") (pinfunction "I7_8") (pintype "input"))
    )
    (net (code "84") (name "DOTCLK") (class "Default")
      (node (ref "U6") (pin "1") (pinfunction "CLK_1") (pintype "input"))
      (node (ref "X1") (pin "6") (pinfunction "DOTCLK_6") (pintype "bidirectional"))
    )
    (net (code "85") (name "DRV_64ADDR_HI") (class "Default")
      (node (ref "IC1") (pin "1") (pinfunction "G_1") (pintype "input"))
      (node (ref "IC1") (pin "19") (pinfunction "G_19") (pintype "input"))
      (node (ref "IC2") (pin "1") (pinfunction "G_1") (pintype "input"))
      (node (ref "IC2") (pin "19") (pinfunction "G_19") (pintype "input"))
      (node (ref "U18") (pin "18") (pinfunction "O6_18") (pintype "bidirectional"))
    )
    (net (code "86") (name "GND") (class "Default")
      (node (ref "C1") (pin "2") (pinfunction "2_2") (pintype "passive"))
      (node (ref "C10") (pin "2") (pinfunction "2_2") (pintype "passive"))
      (node (ref "C11") (pin "2") (pinfunction "2_2") (pintype "passive"))
      (node (ref "C2") (pin "2") (pinfunction "2_2") (pintype "passive"))
      (node (ref "C3") (pin "2") (pinfunction "2_2") (pintype "passive"))
      (node (ref "C4") (pin "2") (pinfunction "2_2") (pintype "passive"))
      (node (ref "C5") (pin "2") (pinfunction "2_2") (pintype "passive"))
      (node (ref "C6") (pin "2") (pinfunction "2_2") (pintype "passive"))
      (node (ref "C7") (pin "2") (pinfunction "2_2") (pintype "passive"))
      (node (ref "C8") (pin "2") (pinfunction "2_2") (pintype "passive"))
      (node (ref "C9") (pin "2") (pinfunction "2_2") (pintype "passive"))
      (node (ref "IC11") (pin "19") (pinfunction "G_19") (pintype "input"))
      (node (ref "IC11") (pin "8") (pinfunction "A4_8") (pintype "input"))
      (node (ref "IC16") (pin "20") (pinfunction "~{CS}_20") (pintype "input"))
      (node (ref "IC17") (pin "20") (pinfunction "~{CS}_20") (pintype "input"))
      (node (ref "IC18") (pin "14") (pinfunction "VSS_14") (pintype "power_in"))
      (node (ref "IC18") (pin "20") (pinfunction "~{CE}_20") (pintype "input"))
      (node (ref "IC7") (pin "12") (pinfunction "Q4_12") (pintype "input"))
      (node (ref "IC7") (pin "14") (pinfunction "Q5_14") (pintype "input"))
      (node (ref "IC7") (pin "16") (pinfunction "Q6_16") (pintype "input"))
      (node (ref "IC7") (pin "18") (pinfunction "Q7_18") (pintype "input"))
      (node (ref "IC7") (pin "3") (pinfunction "Q0_3") (pintype "input"))
      (node (ref "IC7") (pin "5") (pinfunction "Q1_5") (pintype "input"))
      (node (ref "IC7") (pin "7") (pinfunction "Q2_7") (pintype "input"))
      (node (ref "IC7") (pin "9") (pinfunction "Q3_9") (pintype "input"))
      (node (ref "S5") (pin "1") (pinfunction "P_1") (pintype "passive"))
      (node (ref "S6") (pin "14") (pinfunction "S_14") (pintype "passive"))
      (node (ref "S6") (pin "5") (pinfunction "O_5") (pintype "passive"))
      (node (ref "S6") (pin "6") (pinfunction "P_6") (pintype "passive"))
      (node (ref "U6") (pin "11") (pinfunction "OE_11") (pintype "input"))
    )
    (net (code "87") (name "IC15O0") (class "Default")
      (node (ref "IC9") (pin "4") (pinfunction "PRE_4") (pintype "input"))
      (node (ref "U6") (pin "12") (pinfunction "O0_12") (pintype "bidirectional"))
    )
    (net (code "88") (name "IC15O4") (class "Default")
      (node (ref "IC9") (pin "2") (pinfunction "D_2") (pintype "input"))
      (node (ref "U18") (pin "5") (pinfunction "I3_5") (pintype "input"))
      (node (ref "U6") (pin "16") (pinfunction "O4_16") (pintype "output"))
    )
    (net (code "89") (name "IC15O6") (class "Default")
      (node (ref "IC10") (pin "2") (pinfunction "I1_2") (pintype "input"))
      (node (ref "U6") (pin "18") (pinfunction "O6_18") (pintype "output"))
    )
    (net (code "90") (name "LATCH_TO_64") (class "Default")
      (node (ref "IC3") (pin "11") (pinfunction "CLK_11") (pintype "input"))
      (node (ref "IC4") (pin "11") (pinfunction "CLK_11") (pintype "input"))
      (node (ref "IC5") (pin "11") (pinfunction "CLK_11") (pintype "input"))
      (node (ref "U6") (pin "19") (pinfunction "O7_19") (pintype "bidirectional"))
    )
    (net (code "91") (name "N$90") (class "Default")
      (node (ref "U18") (pin "11") (pinfunction "OE_11") (pintype "input"))
      (node (ref "U18") (pin "12") (pinfunction "O0_12") (pintype "bidirectional"))
      (node (ref "U18") (pin "7") (pinfunction "I5_7") (pintype "input"))
      (node (ref "U18") (pin "8") (pinfunction "I6_8") (pintype "input"))
      (node (ref "U18") (pin "9") (pinfunction "I7_9") (pintype "input"))
    )
    (net (code "92") (name "Net-(IC10A-O)") (class "Default")
      (node (ref "IC10") (pin "3") (pinfunction "O_3") (pintype "output"))
      (node (ref "IC10") (pin "5") (pinfunction "I1_5") (pintype "input"))
    )
    (net (code "93") (name "Net-(S6A-P)") (class "Default")
      (node (ref "R7") (pin "1") (pinfunction "1_1") (pintype "passive"))
      (node (ref "S6") (pin "13") (pinfunction "P_13") (pintype "passive"))
      (node (ref "S6") (pin "3") (pinfunction "O_3") (pintype "passive"))
    )
    (net (code "94") (name "PHI0") (class "Default")
      (node (ref "IC19") (pin "37") (pinfunction "PHI0_37") (pintype "input"))
      (node (ref "U1") (pin "3") (pinfunction "I2_3") (pintype "input"))
      (node (ref "U4") (pin "2") (pinfunction "I1_2") (pintype "input"))
      (node (ref "U6") (pin "13") (pinfunction "O1_13") (pintype "output"))
    )
    (net (code "95") (name "ROM_SEL") (class "Default")
      (node (ref "R6") (pin "1") (pinfunction "1_1") (pintype "passive"))
      (node (ref "S6") (pin "9") (pinfunction "P_9") (pintype "passive"))
      (node (ref "U1") (pin "9") (pinfunction "I8_9") (pintype "input"))
    )
    (net (code "96") (name "VCC") (class "Default")
      (node (ref "C1") (pin "1") (pinfunction "1_1") (pintype "passive"))
      (node (ref "C10") (pin "1") (pinfunction "1_1") (pintype "passive"))
      (node (ref "C11") (pin "1") (pinfunction "1_1") (pintype "passive"))
      (node (ref "C2") (pin "1") (pinfunction "1_1") (pintype "passive"))
      (node (ref "C3") (pin "1") (pinfunction "1_1") (pintype "passive"))
      (node (ref "C4") (pin "1") (pinfunction "1_1") (pintype "passive"))
      (node (ref "C5") (pin "1") (pinfunction "1_1") (pintype "passive"))
      (node (ref "C6") (pin "1") (pinfunction "1_1") (pintype "passive"))
      (node (ref "C7") (pin "1") (pinfunction "1_1") (pintype "passive"))
      (node (ref "C8") (pin "1") (pinfunction "1_1") (pintype "passive"))
      (node (ref "C9") (pin "1") (pinfunction "1_1") (pintype "passive"))
      (node (ref "IC1") (pin "11") (pinfunction "A1_11") (pintype "input"))
      (node (ref "IC1") (pin "13") (pinfunction "A2_13") (pintype "input"))
      (node (ref "IC1") (pin "15") (pinfunction "A3_15") (pintype "input"))
      (node (ref "IC1") (pin "17") (pinfunction "A4_17") (pintype "input"))
      (node (ref "IC1") (pin "2") (pinfunction "A1_2") (pintype "input"))
      (node (ref "IC1") (pin "4") (pinfunction "A2_4") (pintype "input"))
      (node (ref "IC1") (pin "6") (pinfunction "A3_6") (pintype "input"))
      (node (ref "IC1") (pin "8") (pinfunction "A4_8") (pintype "input"))
      (node (ref "IC18") (pin "28") (pinfunction "VCC_28") (pintype "power_in"))
      (node (ref "IC2") (pin "11") (pinfunction "A1_11") (pintype "input"))
      (node (ref "IC2") (pin "13") (pinfunction "A2_13") (pintype "input"))
      (node (ref "IC2") (pin "15") (pinfunction "A3_15") (pintype "input"))
      (node (ref "IC2") (pin "17") (pinfunction "A4_17") (pintype "input"))
      (node (ref "IC2") (pin "2") (pinfunction "A1_2") (pintype "input"))
      (node (ref "IC2") (pin "4") (pinfunction "A2_4") (pintype "input"))
      (node (ref "IC2") (pin "6") (pinfunction "A3_6") (pintype "input"))
      (node (ref "IC2") (pin "8") (pinfunction "A4_8") (pintype "input"))
      (node (ref "R1") (pin "2") (pinfunction "2_2") (pintype "passive"))
      (node (ref "R2") (pin "2") (pinfunction "2_2") (pintype "passive"))
      (node (ref "R3") (pin "2") (pinfunction "2_2") (pintype "passive"))
      (node (ref "R4") (pin "2") (pinfunction "2_2") (pintype "passive"))
      (node (ref "R5") (pin "2") (pinfunction "2_2") (pintype "passive"))
      (node (ref "R6") (pin "2") (pinfunction "2_2") (pintype "passive"))
      (node (ref "R7") (pin "2") (pinfunction "2_2") (pintype "passive"))
      (node (ref "U18") (pin "4") (pinfunction "I2_4") (pintype "input"))
      (node (ref "U18") (pin "6") (pinfunction "I4_6") (pintype "input"))
    )
    (net (code "97") (name "WEAK_HI") (class "Default")
      (node (ref "IC11") (pin "13") (pinfunction "A2_13") (pintype "input"))
      (node (ref "IC11") (pin "17") (pinfunction "A4_17") (pintype "input"))
      (node (ref "IC11") (pin "2") (pinfunction "A1_2") (pintype "input"))
      (node (ref "IC11") (pin "4") (pinfunction "A2_4") (pintype "input"))
      (node (ref "IC8") (pin "13") (pinfunction "5D_13") (pintype "input"))
      (node (ref "IC8") (pin "14") (pinfunction "6D_14") (pintype "input"))
      (node (ref "IC8") (pin "17") (pinfunction "7D_17") (pintype "input"))
      (node (ref "IC8") (pin "18") (pinfunction "8D_18") (pintype "input"))
      (node (ref "IC8") (pin "3") (pinfunction "1D_3") (pintype "input"))
      (node (ref "IC9") (pin "1") (pinfunction "CLR_1") (pintype "input"))
      (node (ref "IC9") (pin "10") (pinfunction "PRE_10") (pintype "input"))
      (node (ref "R1") (pin "1") (pinfunction "1_1") (pintype "passive"))
      (node (ref "U6") (pin "3") (pinfunction "I1_3") (pintype "input"))
      (node (ref "U6") (pin "6") (pinfunction "I4_6") (pintype "input"))
    )
    (net (code "98") (name "unconnected-(IC8A-1Q-Pad2)") (class "Default")
      (node (ref "IC8") (pin "2") (pinfunction "1Q_2") (pintype "tri_state"))
    )
    (net (code "99") (name "unconnected-(IC8A-5Q-Pad12)") (class "Default")
      (node (ref "IC8") (pin "12") (pinfunction "5Q_12") (pintype "tri_state"))
    )
    (net (code "100") (name "unconnected-(IC8A-6Q-Pad15)") (class "Default")
      (node (ref "IC8") (pin "15") (pinfunction "6Q_15") (pintype "tri_state"))
    )
    (net (code "101") (name "unconnected-(IC8A-7Q-Pad16)") (class "Default")
      (node (ref "IC8") (pin "16") (pinfunction "7Q_16") (pintype "tri_state"))
    )
    (net (code "102") (name "unconnected-(IC8A-8Q-Pad19)") (class "Default")
      (node (ref "IC8") (pin "19") (pinfunction "8Q_19") (pintype "tri_state"))
    )
    (net (code "103") (name "unconnected-(IC9A-~{Q}-Pad6)") (class "Default")
      (node (ref "IC9") (pin "6") (pinfunction "~{Q}_6") (pintype "output"))
    )
    (net (code "104") (name "unconnected-(IC9B-~{Q}-Pad8)") (class "Default")
      (node (ref "IC9") (pin "8") (pinfunction "~{Q}_8") (pintype "output"))
    )
    (net (code "105") (name "unconnected-(IC11A-Y1-Pad18)") (class "Default")
      (node (ref "IC11") (pin "18") (pinfunction "Y1_18") (pintype "tri_state"))
    )
    (net (code "106") (name "unconnected-(IC11A-Y2-Pad16)") (class "Default")
      (node (ref "IC11") (pin "16") (pinfunction "Y2_16") (pintype "tri_state"))
    )
    (net (code "107") (name "unconnected-(IC11B-Y2-Pad7)") (class "Default")
      (node (ref "IC11") (pin "7") (pinfunction "Y2_7") (pintype "tri_state"))
    )
    (net (code "108") (name "unconnected-(IC11B-Y4-Pad3)") (class "Default")
      (node (ref "IC11") (pin "3") (pinfunction "Y4_3") (pintype "tri_state"))
    )
    (net (code "109") (name "unconnected-(IC18-VPP-Pad1)") (class "Default")
      (node (ref "IC18") (pin "1") (pinfunction "VPP_1") (pintype "input"))
    )
    (net (code "110") (name "unconnected-(IC19A-PHI1-Pad3)") (class "Default")
      (node (ref "IC19") (pin "3") (pinfunction "PHI1_3") (pintype "output"))
    )
    (net (code "111") (name "unconnected-(IC19A-PHI2-Pad39)") (class "Default")
      (node (ref "IC19") (pin "39") (pinfunction "PHI2_39") (pintype "output"))
    )
    (net (code "112") (name "unconnected-(IC19A-SYNC-Pad7)") (class "Default")
      (node (ref "IC19") (pin "7") (pinfunction "SYNC_7") (pintype "output"))
    )
    (net (code "113") (name "unconnected-(S6A-O-Pad1)") (class "Default")
      (node (ref "S6") (pin "1") (pinfunction "O_1") (pintype "passive"))
    )
    (net (code "114") (name "unconnected-(S6C-S-Pad10)") (class "Default")
      (node (ref "S6") (pin "10") (pinfunction "S_10") (pintype "passive"))
    )
    (net (code "115") (name "unconnected-(S6D-O-Pad7)") (class "Default")
      (node (ref "S6") (pin "7") (pinfunction "O_7") (pintype "passive"))
    )
    (net (code "116") (name "unconnected-(U4A-O0-Pad12)") (class "Default")
      (node (ref "U4") (pin "12") (pinfunction "O0_12") (pintype "output"))
    )
    (net (code "117") (name "unconnected-(U4A-O1-Pad13)") (class "Default")
      (node (ref "U4") (pin "13") (pinfunction "O1_13") (pintype "bidirectional"))
    )
    (net (code "118") (name "unconnected-(U6A-O2-Pad14)") (class "Default")
      (node (ref "U6") (pin "14") (pinfunction "O2_14") (pintype "output"))
    )
    (net (code "119") (name "unconnected-(U6A-O5-Pad17)") (class "Default")
      (node (ref "U6") (pin "17") (pinfunction "O5_17") (pintype "output"))
    )
    (net (code "120") (name "unconnected-(U18A-O1-Pad13)") (class "Default")
      (node (ref "U18") (pin "13") (pinfunction "O1_13") (pintype "bidirectional"))
    )
    (net (code "121") (name "unconnected-(U18A-O2-Pad14)") (class "Default")
      (node (ref "U18") (pin "14") (pinfunction "O2_14") (pintype "output"))
    )
    (net (code "122") (name "unconnected-(U18A-O3-Pad15)") (class "Default")
      (node (ref "U18") (pin "15") (pinfunction "O3_15") (pintype "output"))
    )
    (net (code "123") (name "unconnected-(U18A-O4-Pad16)") (class "Default")
      (node (ref "U18") (pin "16") (pinfunction "O4_16") (pintype "output"))
    )
    (net (code "124") (name "unconnected-(U18A-O5-Pad17)") (class "Default")
      (node (ref "U18") (pin "17") (pinfunction "O5_17") (pintype "output"))
    )
    (net (code "125") (name "unconnected-(X1G-~{EXROM}-Pad9)") (class "Default")
      (node (ref "X1") (pin "9") (pinfunction "~{EXROM}_9") (pintype "bidirectional"))
    )
    (net (code "126") (name "unconnected-(X1G-~{GAME}-Pad8)") (class "Default")
      (node (ref "X1") (pin "8") (pinfunction "~{GAME}_8") (pintype "bidirectional"))
    )
    (net (code "127") (name "unconnected-(X1G-~{IO1}-Pad7)") (class "Default")
      (node (ref "X1") (pin "7") (pinfunction "~{IO1}_7") (pintype "bidirectional"))
    )
    (net (code "128") (name "unconnected-(X1G-~{IO2}-Pad10)") (class "Default")
      (node (ref "X1") (pin "10") (pinfunction "~{IO2}_10") (pintype "bidirectional"))
    )
    (net (code "129") (name "unconnected-(X1G-~{ROMH}-PadB)") (class "Default")
      (node (ref "X1") (pin "B") (pinfunction "~{ROMH}_B") (pintype "bidirectional"))
    )
    (net (code "130") (name "unconnected-(X1G-~{ROML}-Pad11)") (class "Default")
      (node (ref "X1") (pin "11") (pinfunction "~{ROML}_11") (pintype "bidirectional"))
    )
  )
)
